# XILINX_XC6SLX9.net
KiCad netlist of a schematic drawn in EAGLE
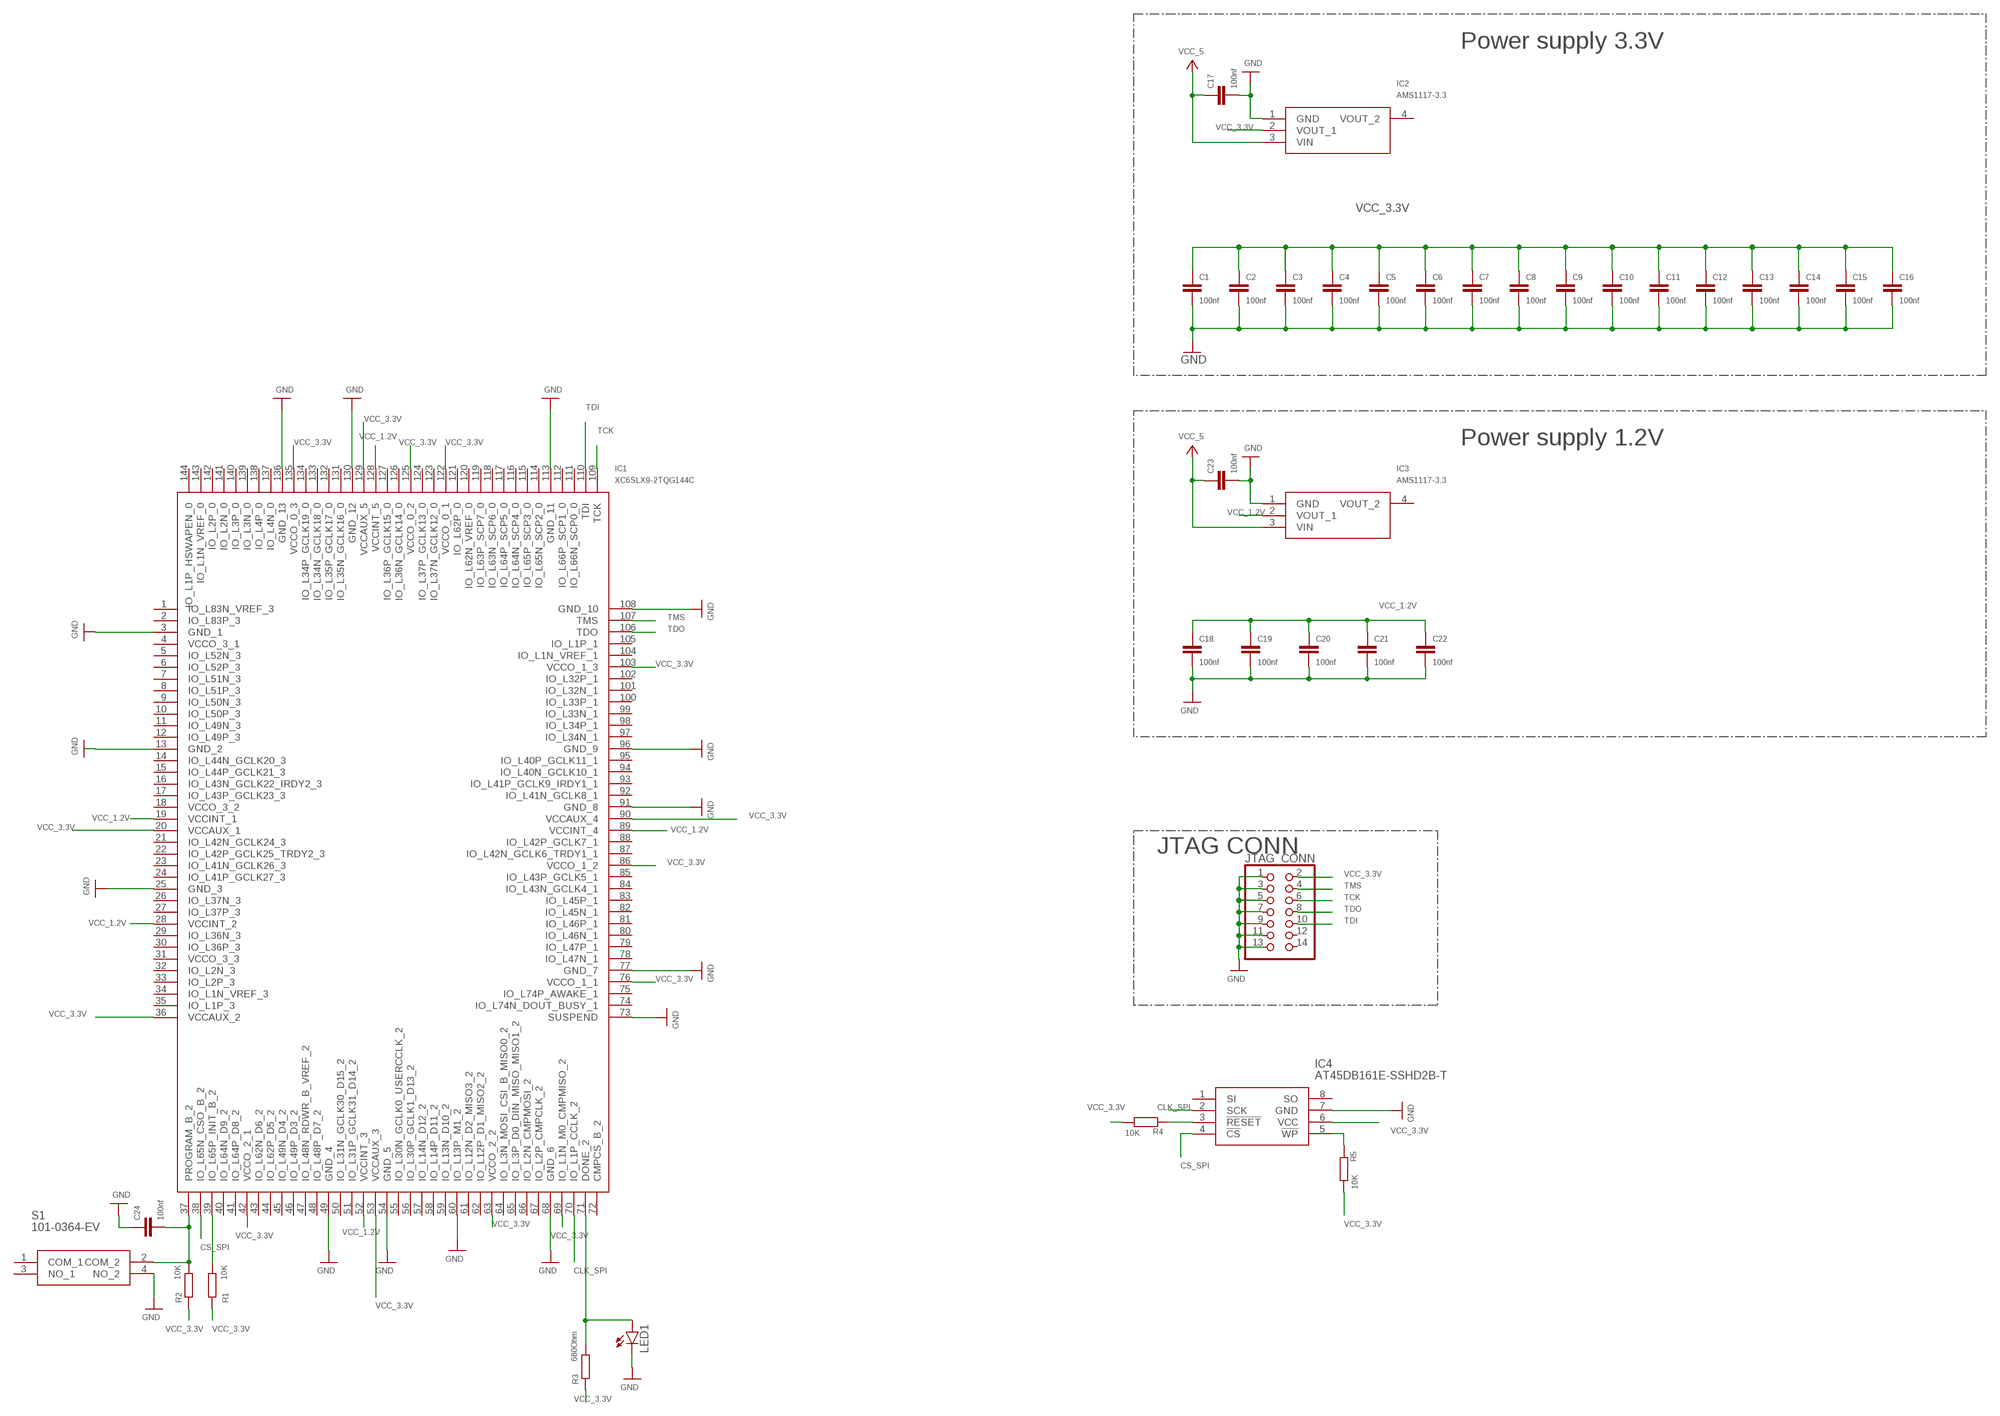
[diagram p0: schematic, sheet 1]

(export (version "E")
  (design (tool "Eeschema 10.0.6"))
  (components
    (comp (ref "C1")
      (value "100nf")
      (footprint "eagle-import:C0805")
      (libsource (lib "eagle-import") (part "C-EUC0805"))
    )
    (comp (ref "C2")
      (value "100nf")
      (footprint "eagle-import:C0805")
      (libsource (lib "eagle-import") (part "C-EUC0805"))
    )
    (comp (ref "C3")
      (value "100nf")
      (footprint "eagle-import:C0805")
      (libsource (lib "eagle-import") (part "C-EUC0805"))
    )
    (comp (ref "C4")
      (value "100nf")
      (footprint "eagle-import:C0805")
      (libsource (lib "eagle-import") (part "C-EUC0805"))
    )
    (comp (ref "C5")
      (value "100nf")
      (footprint "eagle-import:C0805")
      (libsource (lib "eagle-import") (part "C-EUC0805"))
    )
    (comp (ref "C6")
      (value "100nf")
      (footprint "eagle-import:C0805")
      (libsource (lib "eagle-import") (part "C-EUC0805"))
    )
    (comp (ref "C7")
      (value "100nf")
      (footprint "eagle-import:C0805")
      (libsource (lib "eagle-import") (part "C-EUC0805"))
    )
    (comp (ref "C8")
      (value "100nf")
      (footprint "eagle-import:C0805")
      (libsource (lib "eagle-import") (part "C-EUC0805"))
    )
    (comp (ref "C9")
      (value "100nf")
      (footprint "eagle-import:C0805")
      (libsource (lib "eagle-import") (part "C-EUC0805"))
    )
    (comp (ref "C10")
      (value "100nf")
      (footprint "eagle-import:C0805")
      (libsource (lib "eagle-import") (part "C-EUC0805"))
    )
    (comp (ref "C11")
      (value "100nf")
      (footprint "eagle-import:C0805")
      (libsource (lib "eagle-import") (part "C-EUC0805"))
    )
    (comp (ref "C12")
      (value "100nf")
      (footprint "eagle-import:C0805")
      (libsource (lib "eagle-import") (part "C-EUC0805"))
    )
    (comp (ref "C13")
      (value "100nf")
      (footprint "eagle-import:C0805")
      (libsource (lib "eagle-import") (part "C-EUC0805"))
    )
    (comp (ref "C14")
      (value "100nf")
      (footprint "eagle-import:C0805")
      (libsource (lib "eagle-import") (part "C-EUC0805"))
    )
    (comp (ref "C15")
      (value "100nf")
      (footprint "eagle-import:C0805")
      (libsource (lib "eagle-import") (part "C-EUC0805"))
    )
    (comp (ref "C16")
      (value "100nf")
      (footprint "eagle-import:C0805")
      (libsource (lib "eagle-import") (part "C-EUC0805"))
    )
    (comp (ref "C17")
      (value "100nf")
      (footprint "eagle-import:C0805")
      (libsource (lib "eagle-import") (part "C-EUC0805"))
    )
    (comp (ref "C18")
      (value "100nf")
      (footprint "eagle-import:C0805")
      (libsource (lib "eagle-import") (part "C-EUC0805"))
    )
    (comp (ref "C19")
      (value "100nf")
      (footprint "eagle-import:C0805")
      (libsource (lib "eagle-import") (part "C-EUC0805"))
    )
    (comp (ref "C20")
      (value "100nf")
      (footprint "eagle-import:C0805")
      (libsource (lib "eagle-import") (part "C-EUC0805"))
    )
    (comp (ref "C21")
      (value "100nf")
      (footprint "eagle-import:C0805")
      (libsource (lib "eagle-import") (part "C-EUC0805"))
    )
    (comp (ref "C22")
      (value "100nf")
      (footprint "eagle-import:C0805")
      (libsource (lib "eagle-import") (part "C-EUC0805"))
    )
    (comp (ref "C23")
      (value "100nf")
      (footprint "eagle-import:C0805")
      (libsource (lib "eagle-import") (part "C-EUC0805"))
    )
    (comp (ref "C24")
      (value "100nf")
      (footprint "eagle-import:C0805")
      (libsource (lib "eagle-import") (part "C-EUC0805"))
    )
    (comp (ref "IC1")
      (value "XC6SLX9-2TQG144C")
      (footprint "eagle-import:QFP50P2200X2200X160-144N")
      (fields (field (name "MOUSER_PART_NUMBER") "217-XC6SLX9-2TQG144C"))
      (libsource (lib "eagle-import") (part "XC6SLX9-2TQG144C"))
    )
    (comp (ref "IC2")
      (value "AMS1117-3.3")
      (footprint "eagle-import:SOT229P700X180-4N")
      (libsource (lib "eagle-import") (part "AMS1117-3.3"))
    )
    (comp (ref "IC3")
      (value "AMS1117-3.3")
      (footprint "eagle-import:SOT229P700X180-4N")
      (libsource (lib "eagle-import") (part "AMS1117-3.3"))
    )
    (comp (ref "IC4")
      (value "AT45DB161E-SSHD2B-T")
      (footprint "eagle-import:SOIC127P600X175-8N")
      (fields (field (name "MOUSER_PART_NUMBER") "556-A45DB161ESSHD2BT"))
      (libsource (lib "eagle-import") (part "AT45DB161E-SSHD2B-T"))
    )
    (comp (ref "JTAG_CONN")
      (value "PINHD-2X7")
      (footprint "eagle-import:2X07")
      (libsource (lib "eagle-import") (part "PINHD-2X7"))
    )
    (comp (ref "LED1")
      (value "LEDCHIP-LED0805")
      (footprint "eagle-import:CHIP-LED0805")
      (libsource (lib "eagle-import") (part "LEDCHIP-LED0805"))
    )
    (comp (ref "R1")
      (value "10K")
      (footprint "eagle-import:R0805")
      (libsource (lib "eagle-import") (part "R-EU_R0805"))
    )
    (comp (ref "R2")
      (value "10K")
      (footprint "eagle-import:R0805")
      (libsource (lib "eagle-import") (part "R-EU_R0805"))
    )
    (comp (ref "R3")
      (value "680Ohm")
      (footprint "eagle-import:R0805")
      (libsource (lib "eagle-import") (part "R-EU_R0805"))
    )
    (comp (ref "R4")
      (value "10K")
      (footprint "eagle-import:R0805")
      (libsource (lib "eagle-import") (part "R-EU_R0805"))
    )
    (comp (ref "R5")
      (value "10K")
      (footprint "eagle-import:R0805")
      (libsource (lib "eagle-import") (part "R-EU_R0805"))
    )
    (comp (ref "S1")
      (value "101-0364-EV")
      (footprint "eagle-import:1010364EV")
      (libsource (lib "eagle-import") (part "101-0364-EV"))
    )
  )
  (nets
    (net (code "1") (name "/CLK_SPI") (class "Default")
      (node (ref "IC1") (pin "70") (pinfunction "IO_L1P_CCLK_2_70") (pintype "bidirectional"))
      (node (ref "IC4") (pin "2") (pinfunction "SCK_2") (pintype "bidirectional"))
    )
    (net (code "2") (name "/CS_SPI") (class "Default")
      (node (ref "IC1") (pin "38") (pinfunction "IO_L65N_CSO_B_2_38") (pintype "bidirectional"))
      (node (ref "IC4") (pin "4") (pinfunction "~{CS}_4") (pintype "bidirectional"))
    )
    (net (code "3") (name "/TCK") (class "Default")
      (node (ref "IC1") (pin "109") (pinfunction "TCK_109") (pintype "bidirectional"))
      (node (ref "JTAG_CONN") (pin "6") (pinfunction "6_6") (pintype "passive"))
    )
    (net (code "4") (name "/TDI") (class "Default")
      (node (ref "IC1") (pin "110") (pinfunction "TDI_110") (pintype "bidirectional"))
      (node (ref "JTAG_CONN") (pin "10") (pinfunction "10_10") (pintype "passive"))
    )
    (net (code "5") (name "/TDO") (class "Default")
      (node (ref "IC1") (pin "106") (pinfunction "TDO_106") (pintype "bidirectional"))
      (node (ref "JTAG_CONN") (pin "8") (pinfunction "8_8") (pintype "passive"))
    )
    (net (code "6") (name "/TMS") (class "Default")
      (node (ref "IC1") (pin "107") (pinfunction "TMS_107") (pintype "bidirectional"))
      (node (ref "JTAG_CONN") (pin "4") (pinfunction "4_4") (pintype "passive"))
    )
    (net (code "7") (name "/VCC_1.2V") (class "Default")
      (node (ref "C18") (pin "1") (pinfunction "1_1") (pintype "passive"))
      (node (ref "C19") (pin "1") (pinfunction "1_1") (pintype "passive"))
      (node (ref "C20") (pin "1") (pinfunction "1_1") (pintype "passive"))
      (node (ref "C21") (pin "1") (pinfunction "1_1") (pintype "passive"))
      (node (ref "C22") (pin "1") (pinfunction "1_1") (pintype "passive"))
      (node (ref "IC1") (pin "128") (pinfunction "VCCINT_5_128") (pintype "bidirectional"))
      (node (ref "IC1") (pin "19") (pinfunction "VCCINT_1_19") (pintype "bidirectional"))
      (node (ref "IC1") (pin "28") (pinfunction "VCCINT_2_28") (pintype "bidirectional"))
      (node (ref "IC1") (pin "52") (pinfunction "VCCINT_3_52") (pintype "bidirectional"))
      (node (ref "IC1") (pin "89") (pinfunction "VCCINT_4_89") (pintype "bidirectional"))
      (node (ref "IC3") (pin "2") (pinfunction "VOUT_1_2") (pintype "bidirectional"))
    )
    (net (code "8") (name "/VCC_3.3V") (class "Default")
      (node (ref "C1") (pin "1") (pinfunction "1_1") (pintype "passive"))
      (node (ref "C10") (pin "1") (pinfunction "1_1") (pintype "passive"))
      (node (ref "C11") (pin "1") (pinfunction "1_1") (pintype "passive"))
      (node (ref "C12") (pin "1") (pinfunction "1_1") (pintype "passive"))
      (node (ref "C13") (pin "1") (pinfunction "1_1") (pintype "passive"))
      (node (ref "C14") (pin "1") (pinfunction "1_1") (pintype "passive"))
      (node (ref "C15") (pin "1") (pinfunction "1_1") (pintype "passive"))
      (node (ref "C16") (pin "1") (pinfunction "1_1") (pintype "passive"))
      (node (ref "C2") (pin "1") (pinfunction "1_1") (pintype "passive"))
      (node (ref "C3") (pin "1") (pinfunction "1_1") (pintype "passive"))
      (node (ref "C4") (pin "1") (pinfunction "1_1") (pintype "passive"))
      (node (ref "C5") (pin "1") (pinfunction "1_1") (pintype "passive"))
      (node (ref "C6") (pin "1") (pinfunction "1_1") (pintype "passive"))
      (node (ref "C7") (pin "1") (pinfunction "1_1") (pintype "passive"))
      (node (ref "C8") (pin "1") (pinfunction "1_1") (pintype "passive"))
      (node (ref "C9") (pin "1") (pinfunction "1_1") (pintype "passive"))
      (node (ref "IC1") (pin "103") (pinfunction "VCCO_1_3_103") (pintype "bidirectional"))
      (node (ref "IC1") (pin "122") (pinfunction "VCCO_0_1_122") (pintype "bidirectional"))
      (node (ref "IC1") (pin "125") (pinfunction "VCCO_0_2_125") (pintype "bidirectional"))
      (node (ref "IC1") (pin "129") (pinfunction "VCCAUX_5_129") (pintype "bidirectional"))
      (node (ref "IC1") (pin "135") (pinfunction "VCCO_0_3_135") (pintype "bidirectional"))
      (node (ref "IC1") (pin "20") (pinfunction "VCCAUX_1_20") (pintype "bidirectional"))
      (node (ref "IC1") (pin "36") (pinfunction "VCCAUX_2_36") (pintype "bidirectional"))
      (node (ref "IC1") (pin "42") (pinfunction "VCCO_2_1_42") (pintype "bidirectional"))
      (node (ref "IC1") (pin "53") (pinfunction "VCCAUX_3_53") (pintype "bidirectional"))
      (node (ref "IC1") (pin "63") (pinfunction "VCCO_2_2_63") (pintype "bidirectional"))
      (node (ref "IC1") (pin "69") (pinfunction "IO_L1N_M0_CMPMISO_2_69") (pintype "bidirectional"))
      (node (ref "IC1") (pin "76") (pinfunction "VCCO_1_1_76") (pintype "bidirectional"))
      (node (ref "IC1") (pin "86") (pinfunction "VCCO_1_2_86") (pintype "bidirectional"))
      (node (ref "IC1") (pin "90") (pinfunction "VCCAUX_4_90") (pintype "bidirectional"))
      (node (ref "IC2") (pin "2") (pinfunction "VOUT_1_2") (pintype "bidirectional"))
      (node (ref "IC4") (pin "6") (pinfunction "VCC_6") (pintype "bidirectional"))
      (node (ref "JTAG_CONN") (pin "2") (pinfunction "2_2") (pintype "passive"))
      (node (ref "R1") (pin "1") (pinfunction "1_1") (pintype "passive"))
      (node (ref "R2") (pin "1") (pinfunction "1_1") (pintype "passive"))
      (node (ref "R3") (pin "1") (pinfunction "1_1") (pintype "passive"))
      (node (ref "R4") (pin "2") (pinfunction "2_2") (pintype "passive"))
      (node (ref "R5") (pin "2") (pinfunction "2_2") (pintype "passive"))
    )
    (net (code "9") (name "GND") (class "Default")
      (node (ref "C1") (pin "2") (pinfunction "2_2") (pintype "passive"))
      (node (ref "C10") (pin "2") (pinfunction "2_2") (pintype "passive"))
      (node (ref "C11") (pin "2") (pinfunction "2_2") (pintype "passive"))
      (node (ref "C12") (pin "2") (pinfunction "2_2") (pintype "passive"))
      (node (ref "C13") (pin "2") (pinfunction "2_2") (pintype "passive"))
      (node (ref "C14") (pin "2") (pinfunction "2_2") (pintype "passive"))
      (node (ref "C15") (pin "2") (pinfunction "2_2") (pintype "passive"))
      (node (ref "C16") (pin "2") (pinfunction "2_2") (pintype "passive"))
      (node (ref "C17") (pin "2") (pinfunction "2_2") (pintype "passive"))
      (node (ref "C18") (pin "2") (pinfunction "2_2") (pintype "passive"))
      (node (ref "C19") (pin "2") (pinfunction "2_2") (pintype "passive"))
      (node (ref "C2") (pin "2") (pinfunction "2_2") (pintype "passive"))
      (node (ref "C20") (pin "2") (pinfunction "2_2") (pintype "passive"))
      (node (ref "C21") (pin "2") (pinfunction "2_2") (pintype "passive"))
      (node (ref "C22") (pin "2") (pinfunction "2_2") (pintype "passive"))
      (node (ref "C23") (pin "2") (pinfunction "2_2") (pintype "passive"))
      (node (ref "C24") (pin "1") (pinfunction "1_1") (pintype "passive"))
      (node (ref "C3") (pin "2") (pinfunction "2_2") (pintype "passive"))
      (node (ref "C4") (pin "2") (pinfunction "2_2") (pintype "passive"))
      (node (ref "C5") (pin "2") (pinfunction "2_2") (pintype "passive"))
      (node (ref "C6") (pin "2") (pinfunction "2_2") (pintype "passive"))
      (node (ref "C7") (pin "2") (pinfunction "2_2") (pintype "passive"))
      (node (ref "C8") (pin "2") (pinfunction "2_2") (pintype "passive"))
      (node (ref "C9") (pin "2") (pinfunction "2_2") (pintype "passive"))
      (node (ref "IC1") (pin "108") (pinfunction "GND_10_108") (pintype "bidirectional"))
      (node (ref "IC1") (pin "113") (pinfunction "GND_11_113") (pintype "bidirectional"))
      (node (ref "IC1") (pin "13") (pinfunction "GND_2_13") (pintype "bidirectional"))
      (node (ref "IC1") (pin "130") (pinfunction "GND_12_130") (pintype "bidirectional"))
      (node (ref "IC1") (pin "136") (pinfunction "GND_13_136") (pintype "bidirectional"))
      (node (ref "IC1") (pin "25") (pinfunction "GND_3_25") (pintype "bidirectional"))
      (node (ref "IC1") (pin "3") (pinfunction "GND_1_3") (pintype "bidirectional"))
      (node (ref "IC1") (pin "49") (pinfunction "GND_4_49") (pintype "bidirectional"))
      (node (ref "IC1") (pin "54") (pinfunction "GND_5_54") (pintype "bidirectional"))
      (node (ref "IC1") (pin "60") (pinfunction "IO_L13P_M1_2_60") (pintype "bidirectional"))
      (node (ref "IC1") (pin "68") (pinfunction "GND_6_68") (pintype "bidirectional"))
      (node (ref "IC1") (pin "73") (pinfunction "SUSPEND_73") (pintype "bidirectional"))
      (node (ref "IC1") (pin "77") (pinfunction "GND_7_77") (pintype "bidirectional"))
      (node (ref "IC1") (pin "91") (pinfunction "GND_8_91") (pintype "bidirectional"))
      (node (ref "IC1") (pin "96") (pinfunction "GND_9_96") (pintype "bidirectional"))
      (node (ref "IC2") (pin "1") (pinfunction "GND_1") (pintype "bidirectional"))
      (node (ref "IC3") (pin "1") (pinfunction "GND_1") (pintype "bidirectional"))
      (node (ref "IC4") (pin "7") (pinfunction "GND_7") (pintype "bidirectional"))
      (node (ref "JTAG_CONN") (pin "1") (pinfunction "1_1") (pintype "passive"))
      (node (ref "JTAG_CONN") (pin "11") (pinfunction "11_11") (pintype "passive"))
      (node (ref "JTAG_CONN") (pin "13") (pinfunction "13_13") (pintype "passive"))
      (node (ref "JTAG_CONN") (pin "3") (pinfunction "3_3") (pintype "passive"))
      (node (ref "JTAG_CONN") (pin "5") (pinfunction "5_5") (pintype "passive"))
      (node (ref "JTAG_CONN") (pin "7") (pinfunction "7_7") (pintype "passive"))
      (node (ref "JTAG_CONN") (pin "9") (pinfunction "9_9") (pintype "passive"))
      (node (ref "LED1") (pin "C") (pinfunction "C_C") (pintype "passive"))
      (node (ref "S1") (pin "4") (pinfunction "NO_2_4") (pintype "bidirectional"))
    )
    (net (code "10") (name "Net-(IC1-DONE_2)") (class "Default")
      (node (ref "IC1") (pin "71") (pinfunction "DONE_2_71") (pintype "bidirectional"))
      (node (ref "LED1") (pin "A") (pinfunction "A_A") (pintype "passive"))
      (node (ref "R3") (pin "2") (pinfunction "2_2") (pintype "passive"))
    )
    (net (code "11") (name "Net-(IC1-IO_L65P_INIT_B_2)") (class "Default")
      (node (ref "IC1") (pin "39") (pinfunction "IO_L65P_INIT_B_2_39") (pintype "bidirectional"))
      (node (ref "R1") (pin "2") (pinfunction "2_2") (pintype "passive"))
    )
    (net (code "12") (name "Net-(IC1-PROGRAM_B_2)") (class "Default")
      (node (ref "C24") (pin "2") (pinfunction "2_2") (pintype "passive"))
      (node (ref "IC1") (pin "37") (pinfunction "PROGRAM_B_2_37") (pintype "bidirectional"))
      (node (ref "R2") (pin "2") (pinfunction "2_2") (pintype "passive"))
      (node (ref "S1") (pin "2") (pinfunction "COM_2_2") (pintype "bidirectional"))
    )
    (net (code "13") (name "Net-(IC4-~{RESET})") (class "Default")
      (node (ref "IC4") (pin "3") (pinfunction "~{RESET}_3") (pintype "bidirectional"))
      (node (ref "R4") (pin "1") (pinfunction "1_1") (pintype "passive"))
    )
    (net (code "14") (name "Net-(IC4-~{WP})") (class "Default")
      (node (ref "IC4") (pin "5") (pinfunction "~{WP}_5") (pintype "bidirectional"))
      (node (ref "R5") (pin "1") (pinfunction "1_1") (pintype "passive"))
    )
    (net (code "15") (name "VCC_5") (class "Default")
      (node (ref "C17") (pin "1") (pinfunction "1_1") (pintype "passive"))
      (node (ref "C23") (pin "1") (pinfunction "1_1") (pintype "passive"))
      (node (ref "IC2") (pin "3") (pinfunction "VIN_3") (pintype "bidirectional"))
      (node (ref "IC3") (pin "3") (pinfunction "VIN_3") (pintype "bidirectional"))
    )
    (net (code "16") (name "unconnected-(IC1-CMPCS_B_2-Pad72)") (class "Default")
      (node (ref "IC1") (pin "72") (pinfunction "CMPCS_B_2_72") (pintype "bidirectional"))
    )
    (net (code "17") (name "unconnected-(IC1-IO_L1N_VREF_0-Pad143)") (class "Default")
      (node (ref "IC1") (pin "143") (pinfunction "IO_L1N_VREF_0_143") (pintype "bidirectional"))
    )
    (net (code "18") (name "unconnected-(IC1-IO_L1N_VREF_1-Pad104)") (class "Default")
      (node (ref "IC1") (pin "104") (pinfunction "IO_L1N_VREF_1_104") (pintype "bidirectional"))
    )
    (net (code "19") (name "unconnected-(IC1-IO_L1N_VREF_3-Pad34)") (class "Default")
      (node (ref "IC1") (pin "34") (pinfunction "IO_L1N_VREF_3_34") (pintype "bidirectional"))
    )
    (net (code "20") (name "unconnected-(IC1-IO_L1P_1-Pad105)") (class "Default")
      (node (ref "IC1") (pin "105") (pinfunction "IO_L1P_1_105") (pintype "bidirectional"))
    )
    (net (code "21") (name "unconnected-(IC1-IO_L1P_3-Pad35)") (class "Default")
      (node (ref "IC1") (pin "35") (pinfunction "IO_L1P_3_35") (pintype "bidirectional"))
    )
    (net (code "22") (name "unconnected-(IC1-IO_L1P_HSWAPEN_0-Pad144)") (class "Default")
      (node (ref "IC1") (pin "144") (pinfunction "IO_L1P_HSWAPEN_0_144") (pintype "bidirectional"))
    )
    (net (code "23") (name "unconnected-(IC1-IO_L2N_0-Pad141)") (class "Default")
      (node (ref "IC1") (pin "141") (pinfunction "IO_L2N_0_141") (pintype "bidirectional"))
    )
    (net (code "24") (name "unconnected-(IC1-IO_L2N_3-Pad32)") (class "Default")
      (node (ref "IC1") (pin "32") (pinfunction "IO_L2N_3_32") (pintype "bidirectional"))
    )
    (net (code "25") (name "unconnected-(IC1-IO_L2N_CMPMOSI_2-Pad66)") (class "Default")
      (node (ref "IC1") (pin "66") (pinfunction "IO_L2N_CMPMOSI_2_66") (pintype "bidirectional"))
    )
    (net (code "26") (name "unconnected-(IC1-IO_L2P_0-Pad142)") (class "Default")
      (node (ref "IC1") (pin "142") (pinfunction "IO_L2P_0_142") (pintype "bidirectional"))
    )
    (net (code "27") (name "unconnected-(IC1-IO_L2P_3-Pad33)") (class "Default")
      (node (ref "IC1") (pin "33") (pinfunction "IO_L2P_3_33") (pintype "bidirectional"))
    )
    (net (code "28") (name "unconnected-(IC1-IO_L2P_CMPCLK_2-Pad67)") (class "Default")
      (node (ref "IC1") (pin "67") (pinfunction "IO_L2P_CMPCLK_2_67") (pintype "bidirectional"))
    )
    (net (code "29") (name "unconnected-(IC1-IO_L3N_0-Pad139)") (class "Default")
      (node (ref "IC1") (pin "139") (pinfunction "IO_L3N_0_139") (pintype "bidirectional"))
    )
    (net (code "30") (name "unconnected-(IC1-IO_L3N_MOSI_CSI_B_MISO0_2-Pad64)") (class "Default")
      (node (ref "IC1") (pin "64") (pinfunction "IO_L3N_MOSI_CSI_B_MISO0_2_64") (pintype "bidirectional"))
    )
    (net (code "31") (name "unconnected-(IC1-IO_L3P_0-Pad140)") (class "Default")
      (node (ref "IC1") (pin "140") (pinfunction "IO_L3P_0_140") (pintype "bidirectional"))
    )
    (net (code "32") (name "unconnected-(IC1-IO_L3P_D0_DIN_MISO_MISO1_2-Pad65)") (class "Default")
      (node (ref "IC1") (pin "65") (pinfunction "IO_L3P_D0_DIN_MISO_MISO1_2_65") (pintype "bidirectional"))
    )
    (net (code "33") (name "unconnected-(IC1-IO_L4N_0-Pad137)") (class "Default")
      (node (ref "IC1") (pin "137") (pinfunction "IO_L4N_0_137") (pintype "bidirectional"))
    )
    (net (code "34") (name "unconnected-(IC1-IO_L4P_0-Pad138)") (class "Default")
      (node (ref "IC1") (pin "138") (pinfunction "IO_L4P_0_138") (pintype "bidirectional"))
    )
    (net (code "35") (name "unconnected-(IC1-IO_L12N_D2_MISO3_2-Pad61)") (class "Default")
      (node (ref "IC1") (pin "61") (pinfunction "IO_L12N_D2_MISO3_2_61") (pintype "bidirectional"))
    )
    (net (code "36") (name "unconnected-(IC1-IO_L12P_D1_MISO2_2-Pad62)") (class "Default")
      (node (ref "IC1") (pin "62") (pinfunction "IO_L12P_D1_MISO2_2_62") (pintype "bidirectional"))
    )
    (net (code "37") (name "unconnected-(IC1-IO_L13N_D10_2-Pad59)") (class "Default")
      (node (ref "IC1") (pin "59") (pinfunction "IO_L13N_D10_2_59") (pintype "bidirectional"))
    )
    (net (code "38") (name "unconnected-(IC1-IO_L14N_D12_2-Pad57)") (class "Default")
      (node (ref "IC1") (pin "57") (pinfunction "IO_L14N_D12_2_57") (pintype "bidirectional"))
    )
    (net (code "39") (name "unconnected-(IC1-IO_L14P_D11_2-Pad58)") (class "Default")
      (node (ref "IC1") (pin "58") (pinfunction "IO_L14P_D11_2_58") (pintype "bidirectional"))
    )
    (net (code "40") (name "unconnected-(IC1-IO_L30N_GCLK0_USERCCLK_2-Pad55)") (class "Default")
      (node (ref "IC1") (pin "55") (pinfunction "IO_L30N_GCLK0_USERCCLK_2_55") (pintype "bidirectional"))
    )
    (net (code "41") (name "unconnected-(IC1-IO_L30P_GCLK1_D13_2-Pad56)") (class "Default")
      (node (ref "IC1") (pin "56") (pinfunction "IO_L30P_GCLK1_D13_2_56") (pintype "bidirectional"))
    )
    (net (code "42") (name "unconnected-(IC1-IO_L31N_GCLK30_D15_2-Pad50)") (class "Default")
      (node (ref "IC1") (pin "50") (pinfunction "IO_L31N_GCLK30_D15_2_50") (pintype "bidirectional"))
    )
    (net (code "43") (name "unconnected-(IC1-IO_L31P_GCLK31_D14_2-Pad51)") (class "Default")
      (node (ref "IC1") (pin "51") (pinfunction "IO_L31P_GCLK31_D14_2_51") (pintype "bidirectional"))
    )
    (net (code "44") (name "unconnected-(IC1-IO_L32N_1-Pad101)") (class "Default")
      (node (ref "IC1") (pin "101") (pinfunction "IO_L32N_1_101") (pintype "bidirectional"))
    )
    (net (code "45") (name "unconnected-(IC1-IO_L32P_1-Pad102)") (class "Default")
      (node (ref "IC1") (pin "102") (pinfunction "IO_L32P_1_102") (pintype "bidirectional"))
    )
    (net (code "46") (name "unconnected-(IC1-IO_L33N_1-Pad99)") (class "Default")
      (node (ref "IC1") (pin "99") (pinfunction "IO_L33N_1_99") (pintype "bidirectional"))
    )
    (net (code "47") (name "unconnected-(IC1-IO_L33P_1-Pad100)") (class "Default")
      (node (ref "IC1") (pin "100") (pinfunction "IO_L33P_1_100") (pintype "bidirectional"))
    )
    (net (code "48") (name "unconnected-(IC1-IO_L34N_1-Pad97)") (class "Default")
      (node (ref "IC1") (pin "97") (pinfunction "IO_L34N_1_97") (pintype "bidirectional"))
    )
    (net (code "49") (name "unconnected-(IC1-IO_L34N_GCLK18_0-Pad133)") (class "Default")
      (node (ref "IC1") (pin "133") (pinfunction "IO_L34N_GCLK18_0_133") (pintype "bidirectional"))
    )
    (net (code "50") (name "unconnected-(IC1-IO_L34P_1-Pad98)") (class "Default")
      (node (ref "IC1") (pin "98") (pinfunction "IO_L34P_1_98") (pintype "bidirectional"))
    )
    (net (code "51") (name "unconnected-(IC1-IO_L34P_GCLK19_0-Pad134)") (class "Default")
      (node (ref "IC1") (pin "134") (pinfunction "IO_L34P_GCLK19_0_134") (pintype "bidirectional"))
    )
    (net (code "52") (name "unconnected-(IC1-IO_L35N_GCLK16_0-Pad131)") (class "Default")
      (node (ref "IC1") (pin "131") (pinfunction "IO_L35N_GCLK16_0_131") (pintype "bidirectional"))
    )
    (net (code "53") (name "unconnected-(IC1-IO_L35P_GCLK17_0-Pad132)") (class "Default")
      (node (ref "IC1") (pin "132") (pinfunction "IO_L35P_GCLK17_0_132") (pintype "bidirectional"))
    )
    (net (code "54") (name "unconnected-(IC1-IO_L36N_3-Pad29)") (class "Default")
      (node (ref "IC1") (pin "29") (pinfunction "IO_L36N_3_29") (pintype "bidirectional"))
    )
    (net (code "55") (name "unconnected-(IC1-IO_L36N_GCLK14_0-Pad126)") (class "Default")
      (node (ref "IC1") (pin "126") (pinfunction "IO_L36N_GCLK14_0_126") (pintype "bidirectional"))
    )
    (net (code "56") (name "unconnected-(IC1-IO_L36P_3-Pad30)") (class "Default")
      (node (ref "IC1") (pin "30") (pinfunction "IO_L36P_3_30") (pintype "bidirectional"))
    )
    (net (code "57") (name "unconnected-(IC1-IO_L36P_GCLK15_0-Pad127)") (class "Default")
      (node (ref "IC1") (pin "127") (pinfunction "IO_L36P_GCLK15_0_127") (pintype "bidirectional"))
    )
    (net (code "58") (name "unconnected-(IC1-IO_L37N_3-Pad26)") (class "Default")
      (node (ref "IC1") (pin "26") (pinfunction "IO_L37N_3_26") (pintype "bidirectional"))
    )
    (net (code "59") (name "unconnected-(IC1-IO_L37N_GCLK12_0-Pad123)") (class "Default")
      (node (ref "IC1") (pin "123") (pinfunction "IO_L37N_GCLK12_0_123") (pintype "bidirectional"))
    )
    (net (code "60") (name "unconnected-(IC1-IO_L37P_3-Pad27)") (class "Default")
      (node (ref "IC1") (pin "27") (pinfunction "IO_L37P_3_27") (pintype "bidirectional"))
    )
    (net (code "61") (name "unconnected-(IC1-IO_L37P_GCLK13_0-Pad124)") (class "Default")
      (node (ref "IC1") (pin "124") (pinfunction "IO_L37P_GCLK13_0_124") (pintype "bidirectional"))
    )
    (net (code "62") (name "unconnected-(IC1-IO_L40N_GCLK10_1-Pad94)") (class "Default")
      (node (ref "IC1") (pin "94") (pinfunction "IO_L40N_GCLK10_1_94") (pintype "bidirectional"))
    )
    (net (code "63") (name "unconnected-(IC1-IO_L40P_GCLK11_1-Pad95)") (class "Default")
      (node (ref "IC1") (pin "95") (pinfunction "IO_L40P_GCLK11_1_95") (pintype "bidirectional"))
    )
    (net (code "64") (name "unconnected-(IC1-IO_L41N_GCLK8_1-Pad92)") (class "Default")
      (node (ref "IC1") (pin "92") (pinfunction "IO_L41N_GCLK8_1_92") (pintype "bidirectional"))
    )
    (net (code "65") (name "unconnected-(IC1-IO_L41N_GCLK26_3-Pad23)") (class "Default")
      (node (ref "IC1") (pin "23") (pinfunction "IO_L41N_GCLK26_3_23") (pintype "bidirectional"))
    )
    (net (code "66") (name "unconnected-(IC1-IO_L41P_GCLK9_IRDY1_1-Pad93)") (class "Default")
      (node (ref "IC1") (pin "93") (pinfunction "IO_L41P_GCLK9_IRDY1_1_93") (pintype "bidirectional"))
    )
    (net (code "67") (name "unconnected-(IC1-IO_L41P_GCLK27_3-Pad24)") (class "Default")
      (node (ref "IC1") (pin "24") (pinfunction "IO_L41P_GCLK27_3_24") (pintype "bidirectional"))
    )
    (net (code "68") (name "unconnected-(IC1-IO_L42N_GCLK6_TRDY1_1-Pad87)") (class "Default")
      (node (ref "IC1") (pin "87") (pinfunction "IO_L42N_GCLK6_TRDY1_1_87") (pintype "bidirectional"))
    )
    (net (code "69") (name "unconnected-(IC1-IO_L42N_GCLK24_3-Pad21)") (class "Default")
      (node (ref "IC1") (pin "21") (pinfunction "IO_L42N_GCLK24_3_21") (pintype "bidirectional"))
    )
    (net (code "70") (name "unconnected-(IC1-IO_L42P_GCLK7_1-Pad88)") (class "Default")
      (node (ref "IC1") (pin "88") (pinfunction "IO_L42P_GCLK7_1_88") (pintype "bidirectional"))
    )
    (net (code "71") (name "unconnected-(IC1-IO_L42P_GCLK25_TRDY2_3-Pad22)") (class "Default")
      (node (ref "IC1") (pin "22") (pinfunction "IO_L42P_GCLK25_TRDY2_3_22") (pintype "bidirectional"))
    )
    (net (code "72") (name "unconnected-(IC1-IO_L43N_GCLK4_1-Pad84)") (class "Default")
      (node (ref "IC1") (pin "84") (pinfunction "IO_L43N_GCLK4_1_84") (pintype "bidirectional"))
    )
    (net (code "73") (name "unconnected-(IC1-IO_L43N_GCLK22_IRDY2_3-Pad16)") (class "Default")
      (node (ref "IC1") (pin "16") (pinfunction "IO_L43N_GCLK22_IRDY2_3_16") (pintype "bidirectional"))
    )
    (net (code "74") (name "unconnected-(IC1-IO_L43P_GCLK5_1-Pad85)") (class "Default")
      (node (ref "IC1") (pin "85") (pinfunction "IO_L43P_GCLK5_1_85") (pintype "bidirectional"))
    )
    (net (code "75") (name "unconnected-(IC1-IO_L43P_GCLK23_3-Pad17)") (class "Default")
      (node (ref "IC1") (pin "17") (pinfunction "IO_L43P_GCLK23_3_17") (pintype "bidirectional"))
    )
    (net (code "76") (name "unconnected-(IC1-IO_L44N_GCLK20_3-Pad14)") (class "Default")
      (node (ref "IC1") (pin "14") (pinfunction "IO_L44N_GCLK20_3_14") (pintype "bidirectional"))
    )
    (net (code "77") (name "unconnected-(IC1-IO_L44P_GCLK21_3-Pad15)") (class "Default")
      (node (ref "IC1") (pin "15") (pinfunction "IO_L44P_GCLK21_3_15") (pintype "bidirectional"))
    )
    (net (code "78") (name "unconnected-(IC1-IO_L45N_1-Pad82)") (class "Default")
      (node (ref "IC1") (pin "82") (pinfunction "IO_L45N_1_82") (pintype "bidirectional"))
    )
    (net (code "79") (name "unconnected-(IC1-IO_L45P_1-Pad83)") (class "Default")
      (node (ref "IC1") (pin "83") (pinfunction "IO_L45P_1_83") (pintype "bidirectional"))
    )
    (net (code "80") (name "unconnected-(IC1-IO_L46N_1-Pad80)") (class "Default")
      (node (ref "IC1") (pin "80") (pinfunction "IO_L46N_1_80") (pintype "bidirectional"))
    )
    (net (code "81") (name "unconnected-(IC1-IO_L46P_1-Pad81)") (class "Default")
      (node (ref "IC1") (pin "81") (pinfunction "IO_L46P_1_81") (pintype "bidirectional"))
    )
    (net (code "82") (name "unconnected-(IC1-IO_L47N_1-Pad78)") (class "Default")
      (node (ref "IC1") (pin "78") (pinfunction "IO_L47N_1_78") (pintype "bidirectional"))
    )
    (net (code "83") (name "unconnected-(IC1-IO_L47P_1-Pad79)") (class "Default")
      (node (ref "IC1") (pin "79") (pinfunction "IO_L47P_1_79") (pintype "bidirectional"))
    )
    (net (code "84") (name "unconnected-(IC1-IO_L48N_RDWR_B_VREF_2-Pad47)") (class "Default")
      (node (ref "IC1") (pin "47") (pinfunction "IO_L48N_RDWR_B_VREF_2_47") (pintype "bidirectional"))
    )
    (net (code "85") (name "unconnected-(IC1-IO_L48P_D7_2-Pad48)") (class "Default")
      (node (ref "IC1") (pin "48") (pinfunction "IO_L48P_D7_2_48") (pintype "bidirectional"))
    )
    (net (code "86") (name "unconnected-(IC1-IO_L49N_3-Pad11)") (class "Default")
      (node (ref "IC1") (pin "11") (pinfunction "IO_L49N_3_11") (pintype "bidirectional"))
    )
    (net (code "87") (name "unconnected-(IC1-IO_L49N_D4_2-Pad45)") (class "Default")
      (node (ref "IC1") (pin "45") (pinfunction "IO_L49N_D4_2_45") (pintype "bidirectional"))
    )
    (net (code "88") (name "unconnected-(IC1-IO_L49P_3-Pad12)") (class "Default")
      (node (ref "IC1") (pin "12") (pinfunction "IO_L49P_3_12") (pintype "bidirectional"))
    )
    (net (code "89") (name "unconnected-(IC1-IO_L49P_D3_2-Pad46)") (class "Default")
      (node (ref "IC1") (pin "46") (pinfunction "IO_L49P_D3_2_46") (pintype "bidirectional"))
    )
    (net (code "90") (name "unconnected-(IC1-IO_L50N_3-Pad9)") (class "Default")
      (node (ref "IC1") (pin "9") (pinfunction "IO_L50N_3_9") (pintype "bidirectional"))
    )
    (net (code "91") (name "unconnected-(IC1-IO_L50P_3-Pad10)") (class "Default")
      (node (ref "IC1") (pin "10") (pinfunction "IO_L50P_3_10") (pintype "bidirectional"))
    )
    (net (code "92") (name "unconnected-(IC1-IO_L51N_3-Pad7)") (class "Default")
      (node (ref "IC1") (pin "7") (pinfunction "IO_L51N_3_7") (pintype "bidirectional"))
    )
    (net (code "93") (name "unconnected-(IC1-IO_L51P_3-Pad8)") (class "Default")
      (node (ref "IC1") (pin "8") (pinfunction "IO_L51P_3_8") (pintype "bidirectional"))
    )
    (net (code "94") (name "unconnected-(IC1-IO_L52N_3-Pad5)") (class "Default")
      (node (ref "IC1") (pin "5") (pinfunction "IO_L52N_3_5") (pintype "bidirectional"))
    )
    (net (code "95") (name "unconnected-(IC1-IO_L52P_3-Pad6)") (class "Default")
      (node (ref "IC1") (pin "6") (pinfunction "IO_L52P_3_6") (pintype "bidirectional"))
    )
    (net (code "96") (name "unconnected-(IC1-IO_L62N_D6_2-Pad43)") (class "Default")
      (node (ref "IC1") (pin "43") (pinfunction "IO_L62N_D6_2_43") (pintype "bidirectional"))
    )
    (net (code "97") (name "unconnected-(IC1-IO_L62N_VREF_0-Pad120)") (class "Default")
      (node (ref "IC1") (pin "120") (pinfunction "IO_L62N_VREF_0_120") (pintype "bidirectional"))
    )
    (net (code "98") (name "unconnected-(IC1-IO_L62P_0-Pad121)") (class "Default")
      (node (ref "IC1") (pin "121") (pinfunction "IO_L62P_0_121") (pintype "bidirectional"))
    )
    (net (code "99") (name "unconnected-(IC1-IO_L62P_D5_2-Pad44)") (class "Default")
      (node (ref "IC1") (pin "44") (pinfunction "IO_L62P_D5_2_44") (pintype "bidirectional"))
    )
    (net (code "100") (name "unconnected-(IC1-IO_L63N_SCP6_0-Pad118)") (class "Default")
      (node (ref "IC1") (pin "118") (pinfunction "IO_L63N_SCP6_0_118") (pintype "bidirectional"))
    )
    (net (code "101") (name "unconnected-(IC1-IO_L63P_SCP7_0-Pad119)") (class "Default")
      (node (ref "IC1") (pin "119") (pinfunction "IO_L63P_SCP7_0_119") (pintype "bidirectional"))
    )
    (net (code "102") (name "unconnected-(IC1-IO_L64N_D9_2-Pad40)") (class "Default")
      (node (ref "IC1") (pin "40") (pinfunction "IO_L64N_D9_2_40") (pintype "bidirectional"))
    )
    (net (code "103") (name "unconnected-(IC1-IO_L64N_SCP4_0-Pad116)") (class "Default")
      (node (ref "IC1") (pin "116") (pinfunction "IO_L64N_SCP4_0_116") (pintype "bidirectional"))
    )
    (net (code "104") (name "unconnected-(IC1-IO_L64P_D8_2-Pad41)") (class "Default")
      (node (ref "IC1") (pin "41") (pinfunction "IO_L64P_D8_2_41") (pintype "bidirectional"))
    )
    (net (code "105") (name "unconnected-(IC1-IO_L64P_SCP5_0-Pad117)") (class "Default")
      (node (ref "IC1") (pin "117") (pinfunction "IO_L64P_SCP5_0_117") (pintype "bidirectional"))
    )
    (net (code "106") (name "unconnected-(IC1-IO_L65N_SCP2_0-Pad114)") (class "Default")
      (node (ref "IC1") (pin "114") (pinfunction "IO_L65N_SCP2_0_114") (pintype "bidirectional"))
    )
    (net (code "107") (name "unconnected-(IC1-IO_L65P_SCP3_0-Pad115)") (class "Default")
      (node (ref "IC1") (pin "115") (pinfunction "IO_L65P_SCP3_0_115") (pintype "bidirectional"))
    )
    (net (code "108") (name "unconnected-(IC1-IO_L66N_SCP0_0-Pad111)") (class "Default")
      (node (ref "IC1") (pin "111") (pinfunction "IO_L66N_SCP0_0_111") (pintype "bidirectional"))
    )
    (net (code "109") (name "unconnected-(IC1-IO_L66P_SCP1_0-Pad112)") (class "Default")
      (node (ref "IC1") (pin "112") (pinfunction "IO_L66P_SCP1_0_112") (pintype "bidirectional"))
    )
    (net (code "110") (name "unconnected-(IC1-IO_L74N_DOUT_BUSY_1-Pad74)") (class "Default")
      (node (ref "IC1") (pin "74") (pinfunction "IO_L74N_DOUT_BUSY_1_74") (pintype "bidirectional"))
    )
    (net (code "111") (name "unconnected-(IC1-IO_L74P_AWAKE_1-Pad75)") (class "Default")
      (node (ref "IC1") (pin "75") (pinfunction "IO_L74P_AWAKE_1_75") (pintype "bidirectional"))
    )
    (net (code "112") (name "unconnected-(IC1-IO_L83N_VREF_3-Pad1)") (class "Default")
      (node (ref "IC1") (pin "1") (pinfunction "IO_L83N_VREF_3_1") (pintype "bidirectional"))
    )
    (net (code "113") (name "unconnected-(IC1-IO_L83P_3-Pad2)") (class "Default")
      (node (ref "IC1") (pin "2") (pinfunction "IO_L83P_3_2") (pintype "bidirectional"))
    )
    (net (code "114") (name "unconnected-(IC1-VCCO_3_1-Pad4)") (class "Default")
      (node (ref "IC1") (pin "4") (pinfunction "VCCO_3_1_4") (pintype "bidirectional"))
    )
    (net (code "115") (name "unconnected-(IC1-VCCO_3_2-Pad18)") (class "Default")
      (node (ref "IC1") (pin "18") (pinfunction "VCCO_3_2_18") (pintype "bidirectional"))
    )
    (net (code "116") (name "unconnected-(IC1-VCCO_3_3-Pad31)") (class "Default")
      (node (ref "IC1") (pin "31") (pinfunction "VCCO_3_3_31") (pintype "bidirectional"))
    )
    (net (code "117") (name "unconnected-(IC2-VOUT_2-Pad4)") (class "Default")
      (node (ref "IC2") (pin "4") (pinfunction "VOUT_2_4") (pintype "bidirectional"))
    )
    (net (code "118") (name "unconnected-(IC3-VOUT_2-Pad4)") (class "Default")
      (node (ref "IC3") (pin "4") (pinfunction "VOUT_2_4") (pintype "bidirectional"))
    )
    (net (code "119") (name "unconnected-(IC4-SI-Pad1)") (class "Default")
      (node (ref "IC4") (pin "1") (pinfunction "SI_1") (pintype "bidirectional"))
    )
    (net (code "120") (name "unconnected-(IC4-SO-Pad8)") (class "Default")
      (node (ref "IC4") (pin "8") (pinfunction "SO_8") (pintype "bidirectional"))
    )
    (net (code "121") (name "unconnected-(JTAG_CONN-Pad12)") (class "Default")
      (node (ref "JTAG_CONN") (pin "12") (pinfunction "12_12") (pintype "passive"))
    )
    (net (code "122") (name "unconnected-(JTAG_CONN-Pad14)") (class "Default")
      (node (ref "JTAG_CONN") (pin "14") (pinfunction "14_14") (pintype "passive"))
    )
    (net (code "123") (name "unconnected-(S1-COM_1-Pad1)") (class "Default")
      (node (ref "S1") (pin "1") (pinfunction "COM_1_1") (pintype "bidirectional"))
    )
    (net (code "124") (name "unconnected-(S1-NO_1-Pad3)") (class "Default")
      (node (ref "S1") (pin "3") (pinfunction "NO_1_3") (pintype "bidirectional"))
    )
  )
)
